# secondaire.net
KiCad netlist of a schematic drawn in EAGLE
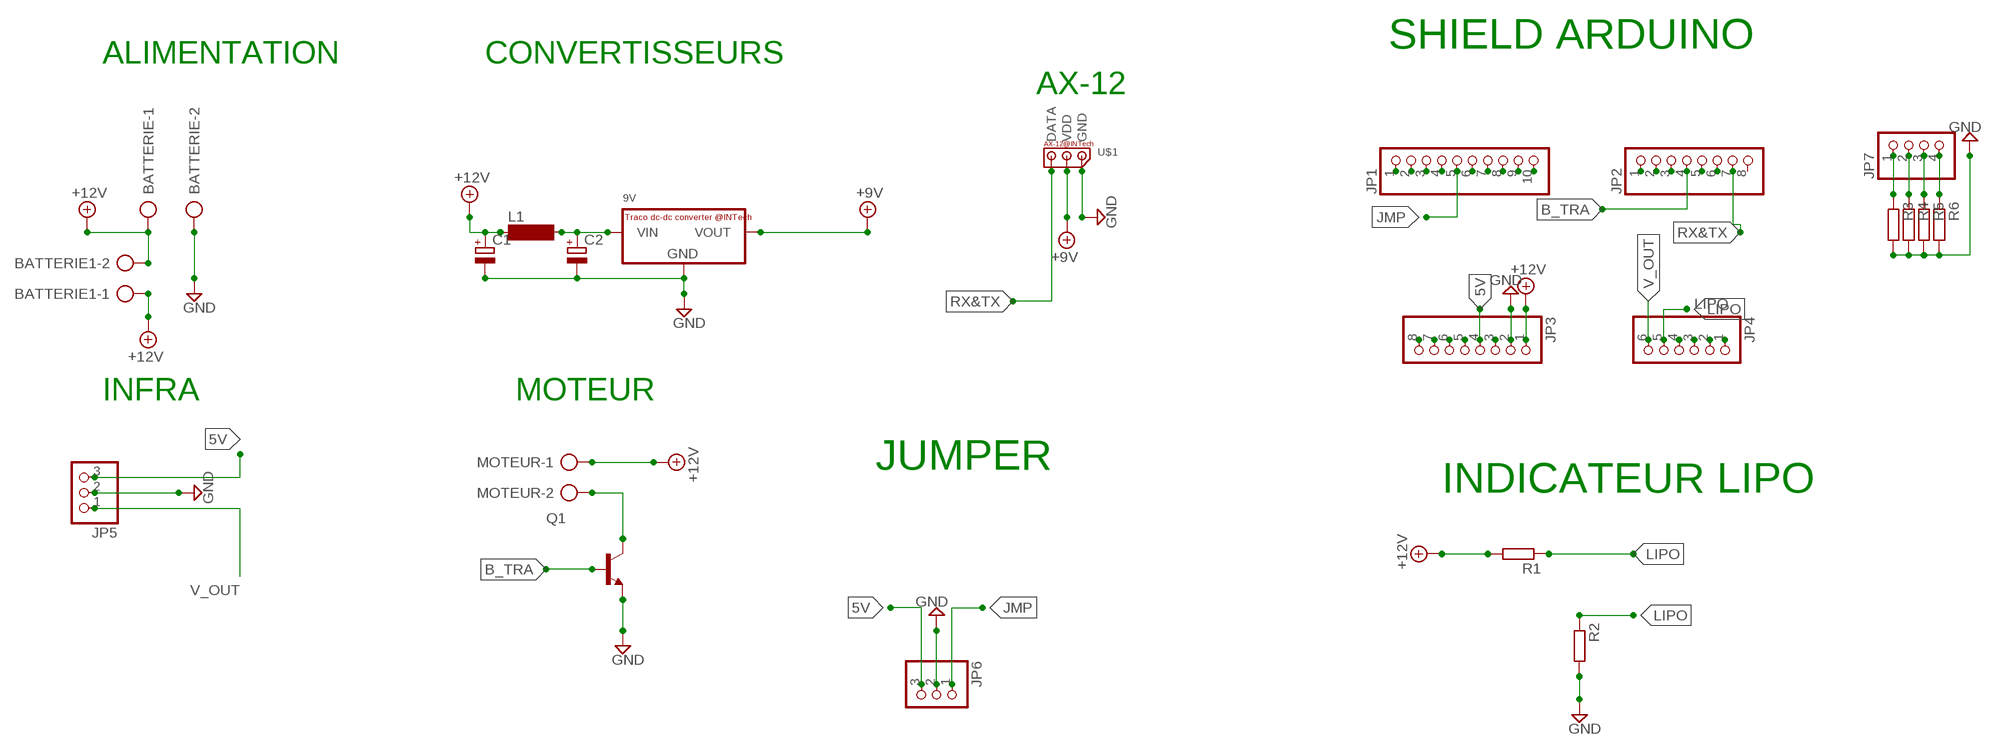
[diagram p0: schematic, sheet 1]

(export (version "E")
  (design (tool "Eeschema 10.0.6"))
  (components
    (comp (ref "9V")
      (value "R-78C-1.0_INTECH")
      (footprint "eagle-import:SIP3_INTECH")
      (libsource (lib "eagle-import") (part "R-78C-1.0_INTECH"))
    )
    (comp (ref "BATTERIE")
      (value "AK300/2")
      (footprint "eagle-import:AK300_2")
      (libsource (lib "eagle-import") (part "AK300/2"))
    )
    (comp (ref "BATTERIE1")
      (value "AK300/2")
      (footprint "eagle-import:AK300_2")
      (fields (field (name "OC_FARNELL") "unknown") (field (name "OC_NEWARK") "unknown"))
      (libsource (lib "eagle-import") (part "AK300/2"))
    )
    (comp (ref "C1")
      (value "CPOL-EUE2.5-6")
      (footprint "eagle-import:E2,5-6")
      (libsource (lib "eagle-import") (part "CPOL-EUE2.5-6"))
    )
    (comp (ref "C2")
      (value "CPOL-EUE2.5-6")
      (footprint "eagle-import:E2,5-6")
      (libsource (lib "eagle-import") (part "CPOL-EUE2.5-6"))
    )
    (comp (ref "JP1")
      (value "PINHD-1X10")
      (footprint "eagle-import:1X10")
      (libsource (lib "eagle-import") (part "PINHD-1X10"))
    )
    (comp (ref "JP2")
      (value "PINHD-1X8")
      (footprint "eagle-import:1X08")
      (libsource (lib "eagle-import") (part "PINHD-1X8"))
    )
    (comp (ref "JP3")
      (value "PINHD-1X8")
      (footprint "eagle-import:1X08")
      (libsource (lib "eagle-import") (part "PINHD-1X8"))
    )
    (comp (ref "JP4")
      (value "PINHD-1X6")
      (footprint "eagle-import:1X06")
      (libsource (lib "eagle-import") (part "PINHD-1X6"))
    )
    (comp (ref "JP5")
      (value "PINHD-1X3")
      (footprint "eagle-import:1X03")
      (libsource (lib "eagle-import") (part "PINHD-1X3"))
    )
    (comp (ref "JP6")
      (value "PINHD-1X3")
      (footprint "eagle-import:1X03")
      (libsource (lib "eagle-import") (part "PINHD-1X3"))
    )
    (comp (ref "JP7")
      (value "PINHD-1X4")
      (footprint "eagle-import:1X04")
      (libsource (lib "eagle-import") (part "PINHD-1X4"))
    )
    (comp (ref "L1")
      (value "SD12-1000")
      (footprint "eagle-import:SD12_1000")
      (libsource (lib "eagle-import") (part "SD12-1000"))
    )
    (comp (ref "MOTEUR")
      (value "AK300/2")
      (footprint "eagle-import:AK300_2")
      (libsource (lib "eagle-import") (part "AK300/2"))
    )
    (comp (ref "Q1")
      (value "BC237-NPN-TO92-CBE")
      (footprint "eagle-import:TO92-CBE")
      (libsource (lib "eagle-import") (part "-NPN-TO92-CBEBC237"))
    )
    (comp (ref "R1")
      (value "R-EU_0204/7")
      (footprint "eagle-import:0204_7")
      (libsource (lib "eagle-import") (part "R-EU_0204/7"))
    )
    (comp (ref "R2")
      (value "R-EU_0204/7")
      (footprint "eagle-import:0204_7")
      (libsource (lib "eagle-import") (part "R-EU_0204/7"))
    )
    (comp (ref "R3")
      (value "R-EU_0204/7")
      (footprint "eagle-import:0204_7")
      (libsource (lib "eagle-import") (part "R-EU_0204/7"))
    )
    (comp (ref "R4")
      (value "R-EU_0204/7")
      (footprint "eagle-import:0204_7")
      (libsource (lib "eagle-import") (part "R-EU_0204/7"))
    )
    (comp (ref "R5")
      (value "R-EU_0204/7")
      (footprint "eagle-import:0204_7")
      (libsource (lib "eagle-import") (part "R-EU_0204/7"))
    )
    (comp (ref "R6")
      (value "R-EU_0204/7")
      (footprint "eagle-import:0204_7")
      (libsource (lib "eagle-import") (part "R-EU_0204/7"))
    )
    (comp (ref "U$1")
      (value "AX-12_CF_INTECH")
      (footprint "eagle-import:AX-12_CF_INTECH")
      (libsource (lib "eagle-import") (part "AX-12_CF_INTECH"))
    )
  )
  (nets
    (net (code "1") (name "+9V") (class "Default")
      (node (ref "9V") (pin "VOUT") (pinfunction "VOUT_VOUT") (pintype "passive"))
      (node (ref "U$1") (pin "VDD") (pinfunction "VDD_VDD") (pintype "passive"))
    )
    (net (code "2") (name "+12V") (class "Default")
      (node (ref "BATTERIE") (pin "1") (pinfunction "KL_1") (pintype "passive"))
      (node (ref "BATTERIE1") (pin "1") (pinfunction "KL_1") (pintype "passive"))
      (node (ref "BATTERIE1") (pin "2") (pinfunction "KL_2") (pintype "passive"))
      (node (ref "C1") (pin "+") (pinfunction "+_+") (pintype "passive"))
      (node (ref "JP3") (pin "1") (pinfunction "1_1") (pintype "passive"))
      (node (ref "L1") (pin "1") (pinfunction "1_1") (pintype "passive"))
      (node (ref "MOTEUR") (pin "1") (pinfunction "KL_1") (pintype "passive"))
      (node (ref "R1") (pin "2") (pinfunction "2_2") (pintype "passive"))
    )
    (net (code "3") (name "5V") (class "Default")
      (node (ref "JP3") (pin "4") (pinfunction "4_4") (pintype "passive"))
      (node (ref "JP5") (pin "3") (pinfunction "3_3") (pintype "passive"))
      (node (ref "JP6") (pin "3") (pinfunction "3_3") (pintype "passive"))
    )
    (net (code "4") (name "B_TRA") (class "Default")
      (node (ref "JP2") (pin "4") (pinfunction "4_4") (pintype "passive"))
      (node (ref "Q1") (pin "B") (pinfunction "B_B") (pintype "passive"))
    )
    (net (code "5") (name "GND") (class "Default")
      (node (ref "9V") (pin "GND") (pinfunction "GND_GND") (pintype "passive"))
      (node (ref "BATTERIE") (pin "2") (pinfunction "KL_2") (pintype "passive"))
      (node (ref "C1") (pin "-") (pinfunction "-_-") (pintype "passive"))
      (node (ref "C2") (pin "-") (pinfunction "-_-") (pintype "passive"))
      (node (ref "JP3") (pin "2") (pinfunction "2_2") (pintype "passive"))
      (node (ref "JP5") (pin "2") (pinfunction "2_2") (pintype "passive"))
      (node (ref "JP6") (pin "2") (pinfunction "2_2") (pintype "passive"))
      (node (ref "Q1") (pin "E") (pinfunction "E_E") (pintype "passive"))
      (node (ref "R2") (pin "2") (pinfunction "2_2") (pintype "passive"))
      (node (ref "R3") (pin "2") (pinfunction "2_2") (pintype "passive"))
      (node (ref "R4") (pin "2") (pinfunction "2_2") (pintype "passive"))
      (node (ref "R5") (pin "2") (pinfunction "2_2") (pintype "passive"))
      (node (ref "R6") (pin "2") (pinfunction "2_2") (pintype "passive"))
      (node (ref "U$1") (pin "GND") (pinfunction "GND_GND") (pintype "passive"))
    )
    (net (code "6") (name "JMP") (class "Default")
      (node (ref "JP1") (pin "5") (pinfunction "5_5") (pintype "passive"))
      (node (ref "JP6") (pin "1") (pinfunction "1_1") (pintype "passive"))
    )
    (net (code "7") (name "LIPO") (class "Default")
      (node (ref "JP4") (pin "5") (pinfunction "5_5") (pintype "passive"))
      (node (ref "R1") (pin "1") (pinfunction "1_1") (pintype "passive"))
      (node (ref "R2") (pin "1") (pinfunction "1_1") (pintype "passive"))
    )
    (net (code "8") (name "Net-(9V-PadVIN)") (class "Default")
      (node (ref "9V") (pin "VIN") (pinfunction "VIN_VIN") (pintype "passive"))
      (node (ref "C2") (pin "+") (pinfunction "+_+") (pintype "passive"))
      (node (ref "L1") (pin "2") (pinfunction "2_2") (pintype "passive"))
    )
    (net (code "9") (name "Net-(JP7-Pad1)") (class "Default")
      (node (ref "JP7") (pin "1") (pinfunction "1_1") (pintype "passive"))
      (node (ref "R3") (pin "1") (pinfunction "1_1") (pintype "passive"))
    )
    (net (code "10") (name "Net-(JP7-Pad2)") (class "Default")
      (node (ref "JP7") (pin "2") (pinfunction "2_2") (pintype "passive"))
      (node (ref "R4") (pin "1") (pinfunction "1_1") (pintype "passive"))
    )
    (net (code "11") (name "Net-(JP7-Pad3)") (class "Default")
      (node (ref "JP7") (pin "3") (pinfunction "3_3") (pintype "passive"))
      (node (ref "R5") (pin "1") (pinfunction "1_1") (pintype "passive"))
    )
    (net (code "12") (name "Net-(JP7-Pad4)") (class "Default")
      (node (ref "JP7") (pin "4") (pinfunction "4_4") (pintype "passive"))
      (node (ref "R6") (pin "1") (pinfunction "1_1") (pintype "passive"))
    )
    (net (code "13") (name "Net-(MOTEURB-KL)") (class "Default")
      (node (ref "MOTEUR") (pin "2") (pinfunction "KL_2") (pintype "passive"))
      (node (ref "Q1") (pin "C") (pinfunction "C_C") (pintype "passive"))
    )
    (net (code "14") (name "RX&TX") (class "Default")
      (node (ref "JP2") (pin "7") (pinfunction "7_7") (pintype "passive"))
      (node (ref "U$1") (pin "DATA") (pinfunction "DATA_DATA") (pintype "passive"))
    )
    (net (code "15") (name "V_OUT") (class "Default")
      (node (ref "JP4") (pin "6") (pinfunction "6_6") (pintype "passive"))
      (node (ref "JP5") (pin "1") (pinfunction "1_1") (pintype "passive"))
    )
    (net (code "16") (name "unconnected-(JP1-Pad1)") (class "Default")
      (node (ref "JP1") (pin "1") (pinfunction "1_1") (pintype "passive"))
    )
    (net (code "17") (name "unconnected-(JP1-Pad2)") (class "Default")
      (node (ref "JP1") (pin "2") (pinfunction "2_2") (pintype "passive"))
    )
    (net (code "18") (name "unconnected-(JP1-Pad3)") (class "Default")
      (node (ref "JP1") (pin "3") (pinfunction "3_3") (pintype "passive"))
    )
    (net (code "19") (name "unconnected-(JP1-Pad4)") (class "Default")
      (node (ref "JP1") (pin "4") (pinfunction "4_4") (pintype "passive"))
    )
    (net (code "20") (name "unconnected-(JP1-Pad6)") (class "Default")
      (node (ref "JP1") (pin "6") (pinfunction "6_6") (pintype "passive"))
    )
    (net (code "21") (name "unconnected-(JP1-Pad7)") (class "Default")
      (node (ref "JP1") (pin "7") (pinfunction "7_7") (pintype "passive"))
    )
    (net (code "22") (name "unconnected-(JP1-Pad8)") (class "Default")
      (node (ref "JP1") (pin "8") (pinfunction "8_8") (pintype "passive"))
    )
    (net (code "23") (name "unconnected-(JP1-Pad9)") (class "Default")
      (node (ref "JP1") (pin "9") (pinfunction "9_9") (pintype "passive"))
    )
    (net (code "24") (name "unconnected-(JP1-Pad10)") (class "Default")
      (node (ref "JP1") (pin "10") (pinfunction "10_10") (pintype "passive"))
    )
    (net (code "25") (name "unconnected-(JP2-Pad1)") (class "Default")
      (node (ref "JP2") (pin "1") (pinfunction "1_1") (pintype "passive"))
    )
    (net (code "26") (name "unconnected-(JP2-Pad2)") (class "Default")
      (node (ref "JP2") (pin "2") (pinfunction "2_2") (pintype "passive"))
    )
    (net (code "27") (name "unconnected-(JP2-Pad3)") (class "Default")
      (node (ref "JP2") (pin "3") (pinfunction "3_3") (pintype "passive"))
    )
    (net (code "28") (name "unconnected-(JP2-Pad5)") (class "Default")
      (node (ref "JP2") (pin "5") (pinfunction "5_5") (pintype "passive"))
    )
    (net (code "29") (name "unconnected-(JP2-Pad6)") (class "Default")
      (node (ref "JP2") (pin "6") (pinfunction "6_6") (pintype "passive"))
    )
    (net (code "30") (name "unconnected-(JP2-Pad8)") (class "Default")
      (node (ref "JP2") (pin "8") (pinfunction "8_8") (pintype "passive"))
    )
    (net (code "31") (name "unconnected-(JP3-Pad3)") (class "Default")
      (node (ref "JP3") (pin "3") (pinfunction "3_3") (pintype "passive"))
    )
    (net (code "32") (name "unconnected-(JP3-Pad5)") (class "Default")
      (node (ref "JP3") (pin "5") (pinfunction "5_5") (pintype "passive"))
    )
    (net (code "33") (name "unconnected-(JP3-Pad6)") (class "Default")
      (node (ref "JP3") (pin "6") (pinfunction "6_6") (pintype "passive"))
    )
    (net (code "34") (name "unconnected-(JP3-Pad7)") (class "Default")
      (node (ref "JP3") (pin "7") (pinfunction "7_7") (pintype "passive"))
    )
    (net (code "35") (name "unconnected-(JP3-Pad8)") (class "Default")
      (node (ref "JP3") (pin "8") (pinfunction "8_8") (pintype "passive"))
    )
    (net (code "36") (name "unconnected-(JP4-Pad1)") (class "Default")
      (node (ref "JP4") (pin "1") (pinfunction "1_1") (pintype "passive"))
    )
    (net (code "37") (name "unconnected-(JP4-Pad2)") (class "Default")
      (node (ref "JP4") (pin "2") (pinfunction "2_2") (pintype "passive"))
    )
    (net (code "38") (name "unconnected-(JP4-Pad3)") (class "Default")
      (node (ref "JP4") (pin "3") (pinfunction "3_3") (pintype "passive"))
    )
    (net (code "39") (name "unconnected-(JP4-Pad4)") (class "Default")
      (node (ref "JP4") (pin "4") (pinfunction "4_4") (pintype "passive"))
    )
  )
)
